# I2C_Switch.net
KiCad netlist of a schematic drawn in Altium Designer
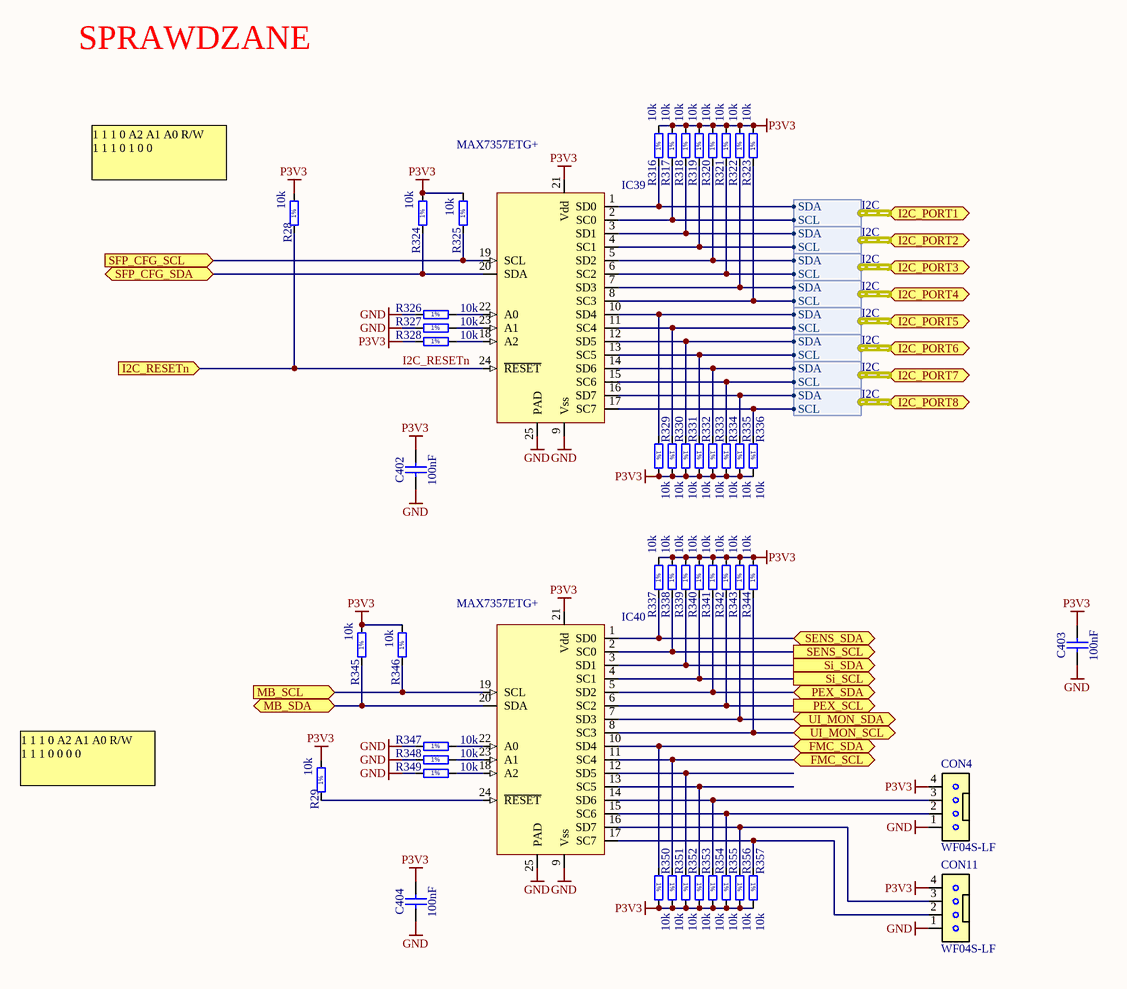
[diagram p0: I2C_Switch.SchDoc]

(export (version "E")
  (design (tool "Eeschema 10.0.6"))
  (components
    (comp (ref "C402")
      (value "100nF")
      (footprint "CAPC0603X33N")
      (description "Non-polarised capacitor")
      (fields
        (field (name "PART NUMBER") "CC0201_100NF_6.3V_10%_X5R")
        (field (name "VOLTAGE") "6.3V")
        (field (name "AUTHOR") "CERN DEM JLC")
      )
      (libsource (lib "Capacitors") (part "Capacitor - non polarized"))
    )
    (comp (ref "C403")
      (value "100nF")
      (footprint "CAPC0603X33N")
      (description "Non-polarised capacitor")
      (fields
        (field (name "PART NUMBER") "CC0201_100NF_6.3V_10%_X5R")
        (field (name "VOLTAGE") "6.3V")
        (field (name "AUTHOR") "CERN DEM JLC")
      )
      (libsource (lib "Capacitors") (part "Capacitor - non polarized"))
    )
    (comp (ref "C404")
      (value "100nF")
      (footprint "CAPC0603X33N")
      (description "Non-polarised capacitor")
      (fields
        (field (name "PART NUMBER") "CC0201_100NF_6.3V_10%_X5R")
        (field (name "VOLTAGE") "6.3V")
        (field (name "AUTHOR") "CERN DEM JLC")
      )
      (libsource (lib "Capacitors") (part "Capacitor - non polarized"))
    )
    (comp (ref "CON4")
      (value "WF04S-LF")
      (footprint "CON_WF04S-LF")
      (libsource (lib "LIBRARY_SCH") (part "CON_4_2.54_key"))
    )
    (comp (ref "CON11")
      (value "WF04S-LF")
      (footprint "CON_WF04S-LF")
      (libsource (lib "LIBRARY_SCH") (part "CON_4_2.54_key"))
    )
    (comp (ref "IC39")
      (value "MAX7357ETG+")
      (footprint "HVQFN24")
      (description "8-channel I2C-bus multiplexer with reset, INT and timeout")
      (libsource (lib "LIBRARY_SCH") (part "IIC_MUX_MAX7357ETG+"))
    )
    (comp (ref "IC40")
      (value "MAX7357ETG+")
      (footprint "HVQFN24")
      (description "8-channel I2C-bus multiplexer with reset, INT and timeout")
      (libsource (lib "LIBRARY_SCH") (part "IIC_MUX_MAX7357ETG+"))
    )
    (comp (ref "R28")
      (value "10k")
      (footprint "RESC1005X40N")
      (description "Resistor - 1%")
      (fields
        (field (name "PART NUMBER") "R0402_10K_1%_0.0625W_100PPM")
        (field (name "POWER") "0.0625W")
        (field (name "AUTHOR") "CERN DEM JLC")
      )
      (libsource (lib "Resistors") (part "Resistor - 1%"))
    )
    (comp (ref "R29")
      (value "10k")
      (footprint "RESC1005X40N")
      (description "Resistor - 1%")
      (fields
        (field (name "PART NUMBER") "R0402_10K_1%_0.0625W_100PPM")
        (field (name "POWER") "0.0625W")
        (field (name "AUTHOR") "CERN DEM JLC")
      )
      (libsource (lib "Resistors") (part "Resistor - 1%"))
    )
    (comp (ref "R316")
      (value "10k")
      (footprint "RESC1005X40N")
      (description "Resistor - 1%")
      (fields
        (field (name "PART NUMBER") "R0402_10K_1%_0.0625W_100PPM")
        (field (name "POWER") "0.0625W")
        (field (name "AUTHOR") "CERN DEM JLC")
      )
      (libsource (lib "Resistors") (part "Resistor - 1%"))
    )
    (comp (ref "R317")
      (value "10k")
      (footprint "RESC1005X40N")
      (description "Resistor - 1%")
      (fields
        (field (name "PART NUMBER") "R0402_10K_1%_0.0625W_100PPM")
        (field (name "POWER") "0.0625W")
        (field (name "AUTHOR") "CERN DEM JLC")
      )
      (libsource (lib "Resistors") (part "Resistor - 1%"))
    )
    (comp (ref "R318")
      (value "10k")
      (footprint "RESC1005X40N")
      (description "Resistor - 1%")
      (fields
        (field (name "PART NUMBER") "R0402_10K_1%_0.0625W_100PPM")
        (field (name "POWER") "0.0625W")
        (field (name "AUTHOR") "CERN DEM JLC")
      )
      (libsource (lib "Resistors") (part "Resistor - 1%"))
    )
    (comp (ref "R319")
      (value "10k")
      (footprint "RESC1005X40N")
      (description "Resistor - 1%")
      (fields
        (field (name "PART NUMBER") "R0402_10K_1%_0.0625W_100PPM")
        (field (name "POWER") "0.0625W")
        (field (name "AUTHOR") "CERN DEM JLC")
      )
      (libsource (lib "Resistors") (part "Resistor - 1%"))
    )
    (comp (ref "R320")
      (value "10k")
      (footprint "RESC1005X40N")
      (description "Resistor - 1%")
      (fields
        (field (name "PART NUMBER") "R0402_10K_1%_0.0625W_100PPM")
        (field (name "POWER") "0.0625W")
        (field (name "AUTHOR") "CERN DEM JLC")
      )
      (libsource (lib "Resistors") (part "Resistor - 1%"))
    )
    (comp (ref "R321")
      (value "10k")
      (footprint "RESC1005X40N")
      (description "Resistor - 1%")
      (fields
        (field (name "PART NUMBER") "R0402_10K_1%_0.0625W_100PPM")
        (field (name "POWER") "0.0625W")
        (field (name "AUTHOR") "CERN DEM JLC")
      )
      (libsource (lib "Resistors") (part "Resistor - 1%"))
    )
    (comp (ref "R322")
      (value "10k")
      (footprint "RESC1005X40N")
      (description "Resistor - 1%")
      (fields
        (field (name "PART NUMBER") "R0402_10K_1%_0.0625W_100PPM")
        (field (name "POWER") "0.0625W")
        (field (name "AUTHOR") "CERN DEM JLC")
      )
      (libsource (lib "Resistors") (part "Resistor - 1%"))
    )
    (comp (ref "R323")
      (value "10k")
      (footprint "RESC1005X40N")
      (description "Resistor - 1%")
      (fields
        (field (name "PART NUMBER") "R0402_10K_1%_0.0625W_100PPM")
        (field (name "POWER") "0.0625W")
        (field (name "AUTHOR") "CERN DEM JLC")
      )
      (libsource (lib "Resistors") (part "Resistor - 1%"))
    )
    (comp (ref "R324")
      (value "10k")
      (footprint "RESC1005X40N")
      (description "Resistor - 1%")
      (fields
        (field (name "PART NUMBER") "R0402_10K_1%_0.0625W_100PPM")
        (field (name "POWER") "0.0625W")
        (field (name "AUTHOR") "CERN DEM JLC")
      )
      (libsource (lib "Resistors") (part "Resistor - 1%"))
    )
    (comp (ref "R325")
      (value "10k")
      (footprint "RESC1005X40N")
      (description "Resistor - 1%")
      (fields
        (field (name "PART NUMBER") "R0402_10K_1%_0.0625W_100PPM")
        (field (name "POWER") "0.0625W")
        (field (name "AUTHOR") "CERN DEM JLC")
      )
      (libsource (lib "Resistors") (part "Resistor - 1%"))
    )
    (comp (ref "R326")
      (value "10k")
      (footprint "RESC1005X40N")
      (description "Resistor - 1%")
      (fields
        (field (name "PART NUMBER") "R0402_10K_1%_0.0625W_100PPM")
        (field (name "POWER") "0.0625W")
        (field (name "AUTHOR") "CERN DEM JLC")
      )
      (libsource (lib "Resistors") (part "Resistor - 1%"))
    )
    (comp (ref "R327")
      (value "10k")
      (footprint "RESC1005X40N")
      (description "Resistor - 1%")
      (fields
        (field (name "PART NUMBER") "R0402_10K_1%_0.0625W_100PPM")
        (field (name "POWER") "0.0625W")
        (field (name "AUTHOR") "CERN DEM JLC")
      )
      (libsource (lib "Resistors") (part "Resistor - 1%"))
    )
    (comp (ref "R328")
      (value "10k")
      (footprint "RESC1005X40N")
      (description "Resistor - 1%")
      (fields
        (field (name "PART NUMBER") "R0402_10K_1%_0.0625W_100PPM")
        (field (name "POWER") "0.0625W")
        (field (name "AUTHOR") "CERN DEM JLC")
      )
      (libsource (lib "Resistors") (part "Resistor - 1%"))
    )
    (comp (ref "R329")
      (value "10k")
      (footprint "RESC1005X40N")
      (description "Resistor - 1%")
      (fields
        (field (name "PART NUMBER") "R0402_10K_1%_0.0625W_100PPM")
        (field (name "POWER") "0.0625W")
        (field (name "AUTHOR") "CERN DEM JLC")
      )
      (libsource (lib "Resistors") (part "Resistor - 1%"))
    )
    (comp (ref "R330")
      (value "10k")
      (footprint "RESC1005X40N")
      (description "Resistor - 1%")
      (fields
        (field (name "PART NUMBER") "R0402_10K_1%_0.0625W_100PPM")
        (field (name "POWER") "0.0625W")
        (field (name "AUTHOR") "CERN DEM JLC")
      )
      (libsource (lib "Resistors") (part "Resistor - 1%"))
    )
    (comp (ref "R331")
      (value "10k")
      (footprint "RESC1005X40N")
      (description "Resistor - 1%")
      (fields
        (field (name "PART NUMBER") "R0402_10K_1%_0.0625W_100PPM")
        (field (name "POWER") "0.0625W")
        (field (name "AUTHOR") "CERN DEM JLC")
      )
      (libsource (lib "Resistors") (part "Resistor - 1%"))
    )
    (comp (ref "R332")
      (value "10k")
      (footprint "RESC1005X40N")
      (description "Resistor - 1%")
      (fields
        (field (name "PART NUMBER") "R0402_10K_1%_0.0625W_100PPM")
        (field (name "POWER") "0.0625W")
        (field (name "AUTHOR") "CERN DEM JLC")
      )
      (libsource (lib "Resistors") (part "Resistor - 1%"))
    )
    (comp (ref "R333")
      (value "10k")
      (footprint "RESC1005X40N")
      (description "Resistor - 1%")
      (fields
        (field (name "PART NUMBER") "R0402_10K_1%_0.0625W_100PPM")
        (field (name "POWER") "0.0625W")
        (field (name "AUTHOR") "CERN DEM JLC")
      )
      (libsource (lib "Resistors") (part "Resistor - 1%"))
    )
    (comp (ref "R334")
      (value "10k")
      (footprint "RESC1005X40N")
      (description "Resistor - 1%")
      (fields
        (field (name "PART NUMBER") "R0402_10K_1%_0.0625W_100PPM")
        (field (name "POWER") "0.0625W")
        (field (name "AUTHOR") "CERN DEM JLC")
      )
      (libsource (lib "Resistors") (part "Resistor - 1%"))
    )
    (comp (ref "R335")
      (value "10k")
      (footprint "RESC1005X40N")
      (description "Resistor - 1%")
      (fields
        (field (name "PART NUMBER") "R0402_10K_1%_0.0625W_100PPM")
        (field (name "POWER") "0.0625W")
        (field (name "AUTHOR") "CERN DEM JLC")
      )
      (libsource (lib "Resistors") (part "Resistor - 1%"))
    )
    (comp (ref "R336")
      (value "10k")
      (footprint "RESC1005X40N")
      (description "Resistor - 1%")
      (fields
        (field (name "PART NUMBER") "R0402_10K_1%_0.0625W_100PPM")
        (field (name "POWER") "0.0625W")
        (field (name "AUTHOR") "CERN DEM JLC")
      )
      (libsource (lib "Resistors") (part "Resistor - 1%"))
    )
    (comp (ref "R337")
      (value "10k")
      (footprint "RESC1005X40N")
      (description "Resistor - 1%")
      (fields
        (field (name "PART NUMBER") "R0402_10K_1%_0.0625W_100PPM")
        (field (name "POWER") "0.0625W")
        (field (name "AUTHOR") "CERN DEM JLC")
      )
      (libsource (lib "Resistors") (part "Resistor - 1%"))
    )
    (comp (ref "R338")
      (value "10k")
      (footprint "RESC1005X40N")
      (description "Resistor - 1%")
      (fields
        (field (name "PART NUMBER") "R0402_10K_1%_0.0625W_100PPM")
        (field (name "POWER") "0.0625W")
        (field (name "AUTHOR") "CERN DEM JLC")
      )
      (libsource (lib "Resistors") (part "Resistor - 1%"))
    )
    (comp (ref "R339")
      (value "10k")
      (footprint "RESC1005X40N")
      (description "Resistor - 1%")
      (fields
        (field (name "PART NUMBER") "R0402_10K_1%_0.0625W_100PPM")
        (field (name "POWER") "0.0625W")
        (field (name "AUTHOR") "CERN DEM JLC")
      )
      (libsource (lib "Resistors") (part "Resistor - 1%"))
    )
    (comp (ref "R340")
      (value "10k")
      (footprint "RESC1005X40N")
      (description "Resistor - 1%")
      (fields
        (field (name "PART NUMBER") "R0402_10K_1%_0.0625W_100PPM")
        (field (name "POWER") "0.0625W")
        (field (name "AUTHOR") "CERN DEM JLC")
      )
      (libsource (lib "Resistors") (part "Resistor - 1%"))
    )
    (comp (ref "R341")
      (value "10k")
      (footprint "RESC1005X40N")
      (description "Resistor - 1%")
      (fields
        (field (name "PART NUMBER") "R0402_10K_1%_0.0625W_100PPM")
        (field (name "POWER") "0.0625W")
        (field (name "AUTHOR") "CERN DEM JLC")
      )
      (libsource (lib "Resistors") (part "Resistor - 1%"))
    )
    (comp (ref "R342")
      (value "10k")
      (footprint "RESC1005X40N")
      (description "Resistor - 1%")
      (fields
        (field (name "PART NUMBER") "R0402_10K_1%_0.0625W_100PPM")
        (field (name "POWER") "0.0625W")
        (field (name "AUTHOR") "CERN DEM JLC")
      )
      (libsource (lib "Resistors") (part "Resistor - 1%"))
    )
    (comp (ref "R343")
      (value "10k")
      (footprint "RESC1005X40N")
      (description "Resistor - 1%")
      (fields
        (field (name "PART NUMBER") "R0402_10K_1%_0.0625W_100PPM")
        (field (name "POWER") "0.0625W")
        (field (name "AUTHOR") "CERN DEM JLC")
      )
      (libsource (lib "Resistors") (part "Resistor - 1%"))
    )
    (comp (ref "R344")
      (value "10k")
      (footprint "RESC1005X40N")
      (description "Resistor - 1%")
      (fields
        (field (name "PART NUMBER") "R0402_10K_1%_0.0625W_100PPM")
        (field (name "POWER") "0.0625W")
        (field (name "AUTHOR") "CERN DEM JLC")
      )
      (libsource (lib "Resistors") (part "Resistor - 1%"))
    )
    (comp (ref "R345")
      (value "10k")
      (footprint "RESC1005X40N")
      (description "Resistor - 1%")
      (fields
        (field (name "PART NUMBER") "R0402_10K_1%_0.0625W_100PPM")
        (field (name "POWER") "0.0625W")
        (field (name "AUTHOR") "CERN DEM JLC")
      )
      (libsource (lib "Resistors") (part "Resistor - 1%"))
    )
    (comp (ref "R346")
      (value "10k")
      (footprint "RESC1005X40N")
      (description "Resistor - 1%")
      (fields
        (field (name "PART NUMBER") "R0402_10K_1%_0.0625W_100PPM")
        (field (name "POWER") "0.0625W")
        (field (name "AUTHOR") "CERN DEM JLC")
      )
      (libsource (lib "Resistors") (part "Resistor - 1%"))
    )
    (comp (ref "R347")
      (value "10k")
      (footprint "RESC1005X40N")
      (description "Resistor - 1%")
      (fields
        (field (name "PART NUMBER") "R0402_10K_1%_0.0625W_100PPM")
        (field (name "POWER") "0.0625W")
        (field (name "AUTHOR") "CERN DEM JLC")
      )
      (libsource (lib "Resistors") (part "Resistor - 1%"))
    )
    (comp (ref "R348")
      (value "10k")
      (footprint "RESC1005X40N")
      (description "Resistor - 1%")
      (fields
        (field (name "PART NUMBER") "R0402_10K_1%_0.0625W_100PPM")
        (field (name "POWER") "0.0625W")
        (field (name "AUTHOR") "CERN DEM JLC")
      )
      (libsource (lib "Resistors") (part "Resistor - 1%"))
    )
    (comp (ref "R349")
      (value "10k")
      (footprint "RESC1005X40N")
      (description "Resistor - 1%")
      (fields
        (field (name "PART NUMBER") "R0402_10K_1%_0.0625W_100PPM")
        (field (name "POWER") "0.0625W")
        (field (name "AUTHOR") "CERN DEM JLC")
      )
      (libsource (lib "Resistors") (part "Resistor - 1%"))
    )
    (comp (ref "R350")
      (value "10k")
      (footprint "RESC1005X40N")
      (description "Resistor - 1%")
      (fields
        (field (name "PART NUMBER") "R0402_10K_1%_0.0625W_100PPM")
        (field (name "POWER") "0.0625W")
        (field (name "AUTHOR") "CERN DEM JLC")
      )
      (libsource (lib "Resistors") (part "Resistor - 1%"))
    )
    (comp (ref "R351")
      (value "10k")
      (footprint "RESC1005X40N")
      (description "Resistor - 1%")
      (fields
        (field (name "PART NUMBER") "R0402_10K_1%_0.0625W_100PPM")
        (field (name "POWER") "0.0625W")
        (field (name "AUTHOR") "CERN DEM JLC")
      )
      (libsource (lib "Resistors") (part "Resistor - 1%"))
    )
    (comp (ref "R352")
      (value "10k")
      (footprint "RESC1005X40N")
      (description "Resistor - 1%")
      (fields
        (field (name "PART NUMBER") "R0402_10K_1%_0.0625W_100PPM")
        (field (name "POWER") "0.0625W")
        (field (name "AUTHOR") "CERN DEM JLC")
      )
      (libsource (lib "Resistors") (part "Resistor - 1%"))
    )
    (comp (ref "R353")
      (value "10k")
      (footprint "RESC1005X40N")
      (description "Resistor - 1%")
      (fields
        (field (name "PART NUMBER") "R0402_10K_1%_0.0625W_100PPM")
        (field (name "POWER") "0.0625W")
        (field (name "AUTHOR") "CERN DEM JLC")
      )
      (libsource (lib "Resistors") (part "Resistor - 1%"))
    )
    (comp (ref "R354")
      (value "10k")
      (footprint "RESC1005X40N")
      (description "Resistor - 1%")
      (fields
        (field (name "PART NUMBER") "R0402_10K_1%_0.0625W_100PPM")
        (field (name "POWER") "0.0625W")
        (field (name "AUTHOR") "CERN DEM JLC")
      )
      (libsource (lib "Resistors") (part "Resistor - 1%"))
    )
    (comp (ref "R355")
      (value "10k")
      (footprint "RESC1005X40N")
      (description "Resistor - 1%")
      (fields
        (field (name "PART NUMBER") "R0402_10K_1%_0.0625W_100PPM")
        (field (name "POWER") "0.0625W")
        (field (name "AUTHOR") "CERN DEM JLC")
      )
      (libsource (lib "Resistors") (part "Resistor - 1%"))
    )
    (comp (ref "R356")
      (value "10k")
      (footprint "RESC1005X40N")
      (description "Resistor - 1%")
      (fields
        (field (name "PART NUMBER") "R0402_10K_1%_0.0625W_100PPM")
        (field (name "POWER") "0.0625W")
        (field (name "AUTHOR") "CERN DEM JLC")
      )
      (libsource (lib "Resistors") (part "Resistor - 1%"))
    )
    (comp (ref "R357")
      (value "10k")
      (footprint "RESC1005X40N")
      (description "Resistor - 1%")
      (fields
        (field (name "PART NUMBER") "R0402_10K_1%_0.0625W_100PPM")
        (field (name "POWER") "0.0625W")
        (field (name "AUTHOR") "CERN DEM JLC")
      )
      (libsource (lib "Resistors") (part "Resistor - 1%"))
    )
  )
  (nets
    (net (code "3") (name "/FMC_SCL") (class "Default")
      (node (ref "IC40") (pin "11") (pinfunction "SC4_11") (pintype "bidirectional"))
      (node (ref "R351") (pin "1") (pinfunction "1_1") (pintype "passive"))
    )
    (net (code "4") (name "/FMC_SDA") (class "Default")
      (node (ref "IC40") (pin "10") (pinfunction "SD4_10") (pintype "bidirectional"))
      (node (ref "R350") (pin "1") (pinfunction "1_1") (pintype "passive"))
    )
    (net (code "6") (name "/I2C_RESETn") (class "Default")
      (node (ref "IC39") (pin "24") (pinfunction "~{RESET}_24") (pintype "input"))
      (node (ref "R28") (pin "1") (pinfunction "1_1") (pintype "passive"))
    )
    (net (code "7") (name "/MB_SCL") (class "Default")
      (node (ref "IC40") (pin "19") (pinfunction "SCL_19") (pintype "input"))
      (node (ref "R346") (pin "1") (pinfunction "1_1") (pintype "passive"))
    )
    (net (code "8") (name "/MB_SDA") (class "Default")
      (node (ref "IC40") (pin "20") (pinfunction "SDA_20") (pintype "bidirectional"))
      (node (ref "R345") (pin "1") (pinfunction "1_1") (pintype "passive"))
    )
    (net (code "9") (name "/PEX_SCL") (class "Default")
      (node (ref "IC40") (pin "6") (pinfunction "SC2_6") (pintype "bidirectional"))
      (node (ref "R342") (pin "1") (pinfunction "1_1") (pintype "passive"))
    )
    (net (code "10") (name "/PEX_SDA") (class "Default")
      (node (ref "IC40") (pin "5") (pinfunction "SD2_5") (pintype "bidirectional"))
      (node (ref "R341") (pin "1") (pinfunction "1_1") (pintype "passive"))
    )
    (net (code "11") (name "/SENS_SCL") (class "Default")
      (node (ref "IC40") (pin "2") (pinfunction "SC0_2") (pintype "bidirectional"))
      (node (ref "R338") (pin "1") (pinfunction "1_1") (pintype "passive"))
    )
    (net (code "12") (name "/SENS_SDA") (class "Default")
      (node (ref "IC40") (pin "1") (pinfunction "SD0_1") (pintype "bidirectional"))
      (node (ref "R337") (pin "1") (pinfunction "1_1") (pintype "passive"))
    )
    (net (code "13") (name "/SFP_CFG_SCL") (class "Default")
      (node (ref "IC39") (pin "19") (pinfunction "SCL_19") (pintype "input"))
      (node (ref "R325") (pin "1") (pinfunction "1_1") (pintype "passive"))
    )
    (net (code "14") (name "/SFP_CFG_SDA") (class "Default")
      (node (ref "IC39") (pin "20") (pinfunction "SDA_20") (pintype "bidirectional"))
      (node (ref "R324") (pin "1") (pinfunction "1_1") (pintype "passive"))
    )
    (net (code "15") (name "/Si_SCL") (class "Default")
      (node (ref "IC40") (pin "4") (pinfunction "SC1_4") (pintype "bidirectional"))
      (node (ref "R340") (pin "1") (pinfunction "1_1") (pintype "passive"))
    )
    (net (code "16") (name "/Si_SDA") (class "Default")
      (node (ref "IC40") (pin "3") (pinfunction "SD1_3") (pintype "bidirectional"))
      (node (ref "R339") (pin "1") (pinfunction "1_1") (pintype "passive"))
    )
    (net (code "17") (name "/UI_MON_SCL") (class "Default")
      (node (ref "IC40") (pin "8") (pinfunction "SC3_8") (pintype "bidirectional"))
      (node (ref "R344") (pin "1") (pinfunction "1_1") (pintype "passive"))
    )
    (net (code "18") (name "/UI_MON_SDA") (class "Default")
      (node (ref "IC40") (pin "7") (pinfunction "SD3_7") (pintype "bidirectional"))
      (node (ref "R343") (pin "1") (pinfunction "1_1") (pintype "passive"))
    )
    (net (code "20") (name "GND") (class "Default")
      (node (ref "C402") (pin "1") (pinfunction "1_1") (pintype "passive"))
      (node (ref "C403") (pin "1") (pinfunction "1_1") (pintype "passive"))
      (node (ref "C404") (pin "1") (pinfunction "1_1") (pintype "passive"))
      (node (ref "CON11") (pin "1") (pinfunction "1_1") (pintype "bidirectional"))
      (node (ref "CON4") (pin "1") (pinfunction "1_1") (pintype "bidirectional"))
      (node (ref "IC39") (pin "25") (pinfunction "PAD_25") (pintype "power_in"))
      (node (ref "IC39") (pin "9") (pinfunction "Vss_9") (pintype "power_in"))
      (node (ref "IC40") (pin "25") (pinfunction "PAD_25") (pintype "power_in"))
      (node (ref "IC40") (pin "9") (pinfunction "Vss_9") (pintype "power_in"))
      (node (ref "R326") (pin "1") (pinfunction "1_1") (pintype "passive"))
      (node (ref "R327") (pin "1") (pinfunction "1_1") (pintype "passive"))
      (node (ref "R347") (pin "1") (pinfunction "1_1") (pintype "passive"))
      (node (ref "R348") (pin "1") (pinfunction "1_1") (pintype "passive"))
      (node (ref "R349") (pin "1") (pinfunction "1_1") (pintype "passive"))
    )
    (net (code "21") (name "Net-(IC39-A0)") (class "Default")
      (node (ref "IC39") (pin "22") (pinfunction "A0_22") (pintype "input"))
      (node (ref "R326") (pin "2") (pinfunction "2_2") (pintype "passive"))
    )
    (net (code "22") (name "Net-(IC39-A1)") (class "Default")
      (node (ref "IC39") (pin "23") (pinfunction "A1_23") (pintype "input"))
      (node (ref "R327") (pin "2") (pinfunction "2_2") (pintype "passive"))
    )
    (net (code "23") (name "Net-(IC39-A2)") (class "Default")
      (node (ref "IC39") (pin "18") (pinfunction "A2_18") (pintype "input"))
      (node (ref "R328") (pin "2") (pinfunction "2_2") (pintype "passive"))
    )
    (net (code "24") (name "Net-(IC39-SC0)") (class "Default")
      (node (ref "IC39") (pin "2") (pinfunction "SC0_2") (pintype "bidirectional"))
      (node (ref "R317") (pin "1") (pinfunction "1_1") (pintype "passive"))
    )
    (net (code "25") (name "Net-(IC39-SC1)") (class "Default")
      (node (ref "IC39") (pin "4") (pinfunction "SC1_4") (pintype "bidirectional"))
      (node (ref "R319") (pin "1") (pinfunction "1_1") (pintype "passive"))
    )
    (net (code "26") (name "Net-(IC39-SC2)") (class "Default")
      (node (ref "IC39") (pin "6") (pinfunction "SC2_6") (pintype "bidirectional"))
      (node (ref "R321") (pin "1") (pinfunction "1_1") (pintype "passive"))
    )
    (net (code "27") (name "Net-(IC39-SC3)") (class "Default")
      (node (ref "IC39") (pin "8") (pinfunction "SC3_8") (pintype "bidirectional"))
      (node (ref "R323") (pin "1") (pinfunction "1_1") (pintype "passive"))
    )
    (net (code "28") (name "Net-(IC39-SC4)") (class "Default")
      (node (ref "IC39") (pin "11") (pinfunction "SC4_11") (pintype "bidirectional"))
      (node (ref "R330") (pin "1") (pinfunction "1_1") (pintype "passive"))
    )
    (net (code "29") (name "Net-(IC39-SC5)") (class "Default")
      (node (ref "IC39") (pin "13") (pinfunction "SC5_13") (pintype "bidirectional"))
      (node (ref "R332") (pin "1") (pinfunction "1_1") (pintype "passive"))
    )
    (net (code "30") (name "Net-(IC39-SC6)") (class "Default")
      (node (ref "IC39") (pin "15") (pinfunction "SC6_15") (pintype "bidirectional"))
      (node (ref "R334") (pin "1") (pinfunction "1_1") (pintype "passive"))
    )
    (net (code "31") (name "Net-(IC39-SC7)") (class "Default")
      (node (ref "IC39") (pin "17") (pinfunction "SC7_17") (pintype "bidirectional"))
      (node (ref "R336") (pin "1") (pinfunction "1_1") (pintype "passive"))
    )
    (net (code "32") (name "Net-(IC39-SD0)") (class "Default")
      (node (ref "IC39") (pin "1") (pinfunction "SD0_1") (pintype "bidirectional"))
      (node (ref "R316") (pin "1") (pinfunction "1_1") (pintype "passive"))
    )
    (net (code "33") (name "Net-(IC39-SD1)") (class "Default")
      (node (ref "IC39") (pin "3") (pinfunction "SD1_3") (pintype "bidirectional"))
      (node (ref "R318") (pin "1") (pinfunction "1_1") (pintype "passive"))
    )
    (net (code "34") (name "Net-(IC39-SD2)") (class "Default")
      (node (ref "IC39") (pin "5") (pinfunction "SD2_5") (pintype "bidirectional"))
      (node (ref "R320") (pin "1") (pinfunction "1_1") (pintype "passive"))
    )
    (net (code "35") (name "Net-(IC39-SD3)") (class "Default")
      (node (ref "IC39") (pin "7") (pinfunction "SD3_7") (pintype "bidirectional"))
      (node (ref "R322") (pin "1") (pinfunction "1_1") (pintype "passive"))
    )
    (net (code "36") (name "Net-(IC39-SD4)") (class "Default")
      (node (ref "IC39") (pin "10") (pinfunction "SD4_10") (pintype "bidirectional"))
      (node (ref "R329") (pin "1") (pinfunction "1_1") (pintype "passive"))
    )
    (net (code "37") (name "Net-(IC39-SD5)") (class "Default")
      (node (ref "IC39") (pin "12") (pinfunction "SD5_12") (pintype "bidirectional"))
      (node (ref "R331") (pin "1") (pinfunction "1_1") (pintype "passive"))
    )
    (net (code "38") (name "Net-(IC39-SD6)") (class "Default")
      (node (ref "IC39") (pin "14") (pinfunction "SD6_14") (pintype "bidirectional"))
      (node (ref "R333") (pin "1") (pinfunction "1_1") (pintype "passive"))
    )
    (net (code "39") (name "Net-(IC39-SD7)") (class "Default")
      (node (ref "IC39") (pin "16") (pinfunction "SD7_16") (pintype "bidirectional"))
      (node (ref "R335") (pin "1") (pinfunction "1_1") (pintype "passive"))
    )
    (net (code "40") (name "Net-(IC40-A0)") (class "Default")
      (node (ref "IC40") (pin "22") (pinfunction "A0_22") (pintype "input"))
      (node (ref "R347") (pin "2") (pinfunction "2_2") (pintype "passive"))
    )
    (net (code "41") (name "Net-(IC40-A1)") (class "Default")
      (node (ref "IC40") (pin "23") (pinfunction "A1_23") (pintype "input"))
      (node (ref "R348") (pin "2") (pinfunction "2_2") (pintype "passive"))
    )
    (net (code "42") (name "Net-(IC40-A2)") (class "Default")
      (node (ref "IC40") (pin "18") (pinfunction "A2_18") (pintype "input"))
      (node (ref "R349") (pin "2") (pinfunction "2_2") (pintype "passive"))
    )
    (net (code "43") (name "Net-(IC40-SC5)") (class "Default")
      (node (ref "IC40") (pin "13") (pinfunction "SC5_13") (pintype "bidirectional"))
      (node (ref "R353") (pin "1") (pinfunction "1_1") (pintype "passive"))
    )
    (net (code "44") (name "Net-(IC40-SC6)") (class "Default")
      (node (ref "CON4") (pin "2") (pinfunction "2_2") (pintype "bidirectional"))
      (node (ref "IC40") (pin "15") (pinfunction "SC6_15") (pintype "bidirectional"))
      (node (ref "R355") (pin "1") (pinfunction "1_1") (pintype "passive"))
    )
    (net (code "45") (name "Net-(IC40-SC7)") (class "Default")
      (node (ref "CON11") (pin "2") (pinfunction "2_2") (pintype "bidirectional"))
      (node (ref "IC40") (pin "17") (pinfunction "SC7_17") (pintype "bidirectional"))
      (node (ref "R357") (pin "1") (pinfunction "1_1") (pintype "passive"))
    )
    (net (code "46") (name "Net-(IC40-SD5)") (class "Default")
      (node (ref "IC40") (pin "12") (pinfunction "SD5_12") (pintype "bidirectional"))
      (node (ref "R352") (pin "1") (pinfunction "1_1") (pintype "passive"))
    )
    (net (code "47") (name "Net-(IC40-SD6)") (class "Default")
      (node (ref "CON4") (pin "3") (pinfunction "3_3") (pintype "bidirectional"))
      (node (ref "IC40") (pin "14") (pinfunction "SD6_14") (pintype "bidirectional"))
      (node (ref "R354") (pin "1") (pinfunction "1_1") (pintype "passive"))
    )
    (net (code "48") (name "Net-(IC40-SD7)") (class "Default")
      (node (ref "CON11") (pin "3") (pinfunction "3_3") (pintype "bidirectional"))
      (node (ref "IC40") (pin "16") (pinfunction "SD7_16") (pintype "bidirectional"))
      (node (ref "R356") (pin "1") (pinfunction "1_1") (pintype "passive"))
    )
    (net (code "49") (name "Net-(IC40-~{RESET})") (class "Default")
      (node (ref "IC40") (pin "24") (pinfunction "~{RESET}_24") (pintype "input"))
      (node (ref "R29") (pin "1") (pinfunction "1_1") (pintype "passive"))
    )
    (net (code "50") (name "P3V3") (class "Default")
      (node (ref "C402") (pin "2") (pinfunction "2_2") (pintype "passive"))
      (node (ref "C403") (pin "2") (pinfunction "2_2") (pintype "passive"))
      (node (ref "C404") (pin "2") (pinfunction "2_2") (pintype "passive"))
      (node (ref "CON11") (pin "4") (pinfunction "4_4") (pintype "bidirectional"))
      (node (ref "CON4") (pin "4") (pinfunction "4_4") (pintype "bidirectional"))
      (node (ref "IC39") (pin "21") (pinfunction "Vdd_21") (pintype "power_in"))
      (node (ref "IC40") (pin "21") (pinfunction "Vdd_21") (pintype "power_in"))
      (node (ref "R28") (pin "2") (pinfunction "2_2") (pintype "passive"))
      (node (ref "R29") (pin "2") (pinfunction "2_2") (pintype "passive"))
      (node (ref "R316") (pin "2") (pinfunction "2_2") (pintype "passive"))
      (node (ref "R317") (pin "2") (pinfunction "2_2") (pintype "passive"))
      (node (ref "R318") (pin "2") (pinfunction "2_2") (pintype "passive"))
      (node (ref "R319") (pin "2") (pinfunction "2_2") (pintype "passive"))
      (node (ref "R320") (pin "2") (pinfunction "2_2") (pintype "passive"))
      (node (ref "R321") (pin "2") (pinfunction "2_2") (pintype "passive"))
      (node (ref "R322") (pin "2") (pinfunction "2_2") (pintype "passive"))
      (node (ref "R323") (pin "2") (pinfunction "2_2") (pintype "passive"))
      (node (ref "R324") (pin "2") (pinfunction "2_2") (pintype "passive"))
      (node (ref "R325") (pin "2") (pinfunction "2_2") (pintype "passive"))
      (node (ref "R328") (pin "1") (pinfunction "1_1") (pintype "passive"))
      (node (ref "R329") (pin "2") (pinfunction "2_2") (pintype "passive"))
      (node (ref "R330") (pin "2") (pinfunction "2_2") (pintype "passive"))
      (node (ref "R331") (pin "2") (pinfunction "2_2") (pintype "passive"))
      (node (ref "R332") (pin "2") (pinfunction "2_2") (pintype "passive"))
      (node (ref "R333") (pin "2") (pinfunction "2_2") (pintype "passive"))
      (node (ref "R334") (pin "2") (pinfunction "2_2") (pintype "passive"))
      (node (ref "R335") (pin "2") (pinfunction "2_2") (pintype "passive"))
      (node (ref "R336") (pin "2") (pinfunction "2_2") (pintype "passive"))
      (node (ref "R337") (pin "2") (pinfunction "2_2") (pintype "passive"))
      (node (ref "R338") (pin "2") (pinfunction "2_2") (pintype "passive"))
      (node (ref "R339") (pin "2") (pinfunction "2_2") (pintype "passive"))
      (node (ref "R340") (pin "2") (pinfunction "2_2") (pintype "passive"))
      (node (ref "R341") (pin "2") (pinfunction "2_2") (pintype "passive"))
      (node (ref "R342") (pin "2") (pinfunction "2_2") (pintype "passive"))
      (node (ref "R343") (pin "2") (pinfunction "2_2") (pintype "passive"))
      (node (ref "R344") (pin "2") (pinfunction "2_2") (pintype "passive"))
      (node (ref "R345") (pin "2") (pinfunction "2_2") (pintype "passive"))
      (node (ref "R346") (pin "2") (pinfunction "2_2") (pintype "passive"))
      (node (ref "R350") (pin "2") (pinfunction "2_2") (pintype "passive"))
      (node (ref "R351") (pin "2") (pinfunction "2_2") (pintype "passive"))
      (node (ref "R352") (pin "2") (pinfunction "2_2") (pintype "passive"))
      (node (ref "R353") (pin "2") (pinfunction "2_2") (pintype "passive"))
      (node (ref "R354") (pin "2") (pinfunction "2_2") (pintype "passive"))
      (node (ref "R355") (pin "2") (pinfunction "2_2") (pintype "passive"))
      (node (ref "R356") (pin "2") (pinfunction "2_2") (pintype "passive"))
      (node (ref "R357") (pin "2") (pinfunction "2_2") (pintype "passive"))
    )
  )
)
